# pcb1.net
KiCad netlist of a schematic drawn in EAGLE
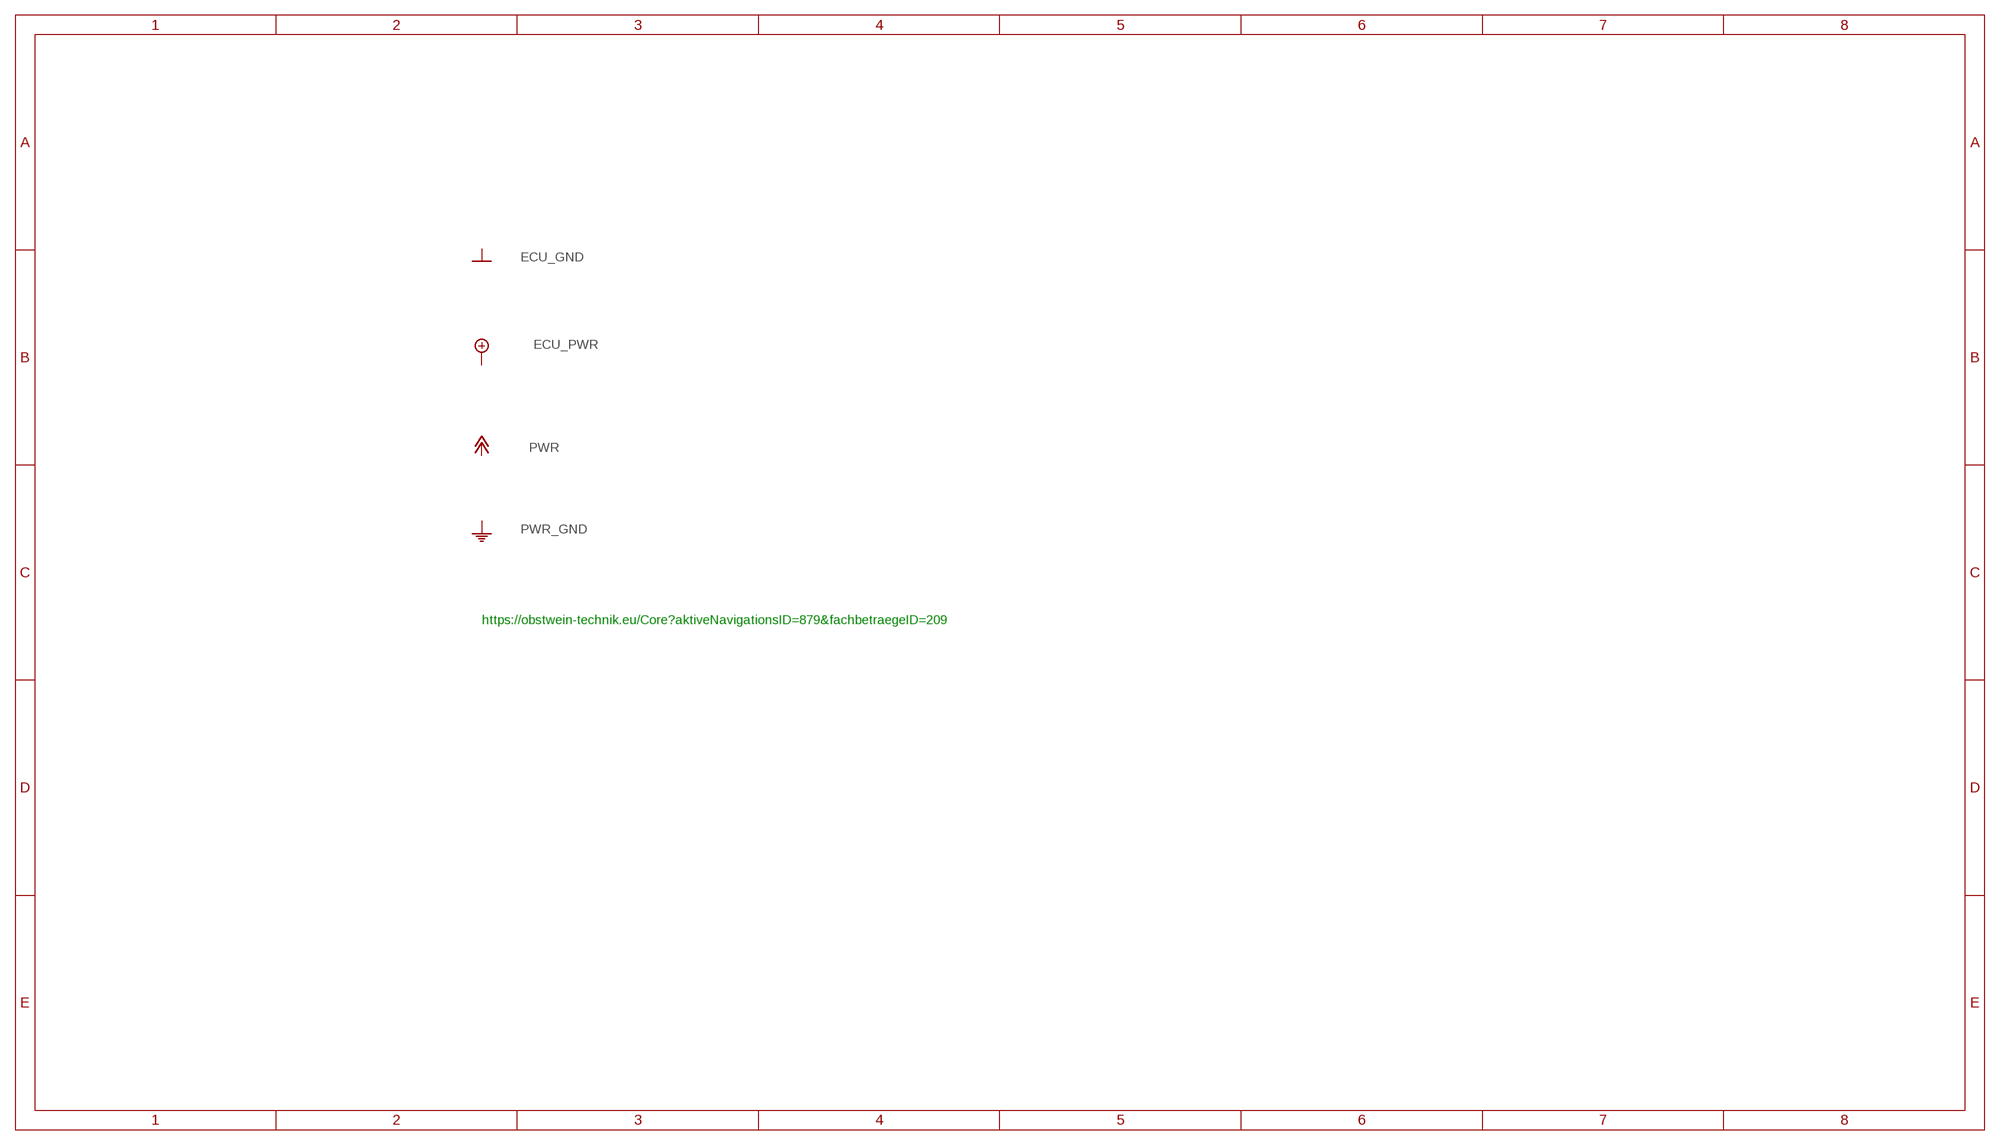
[diagram p0: schematic, sheet 1]
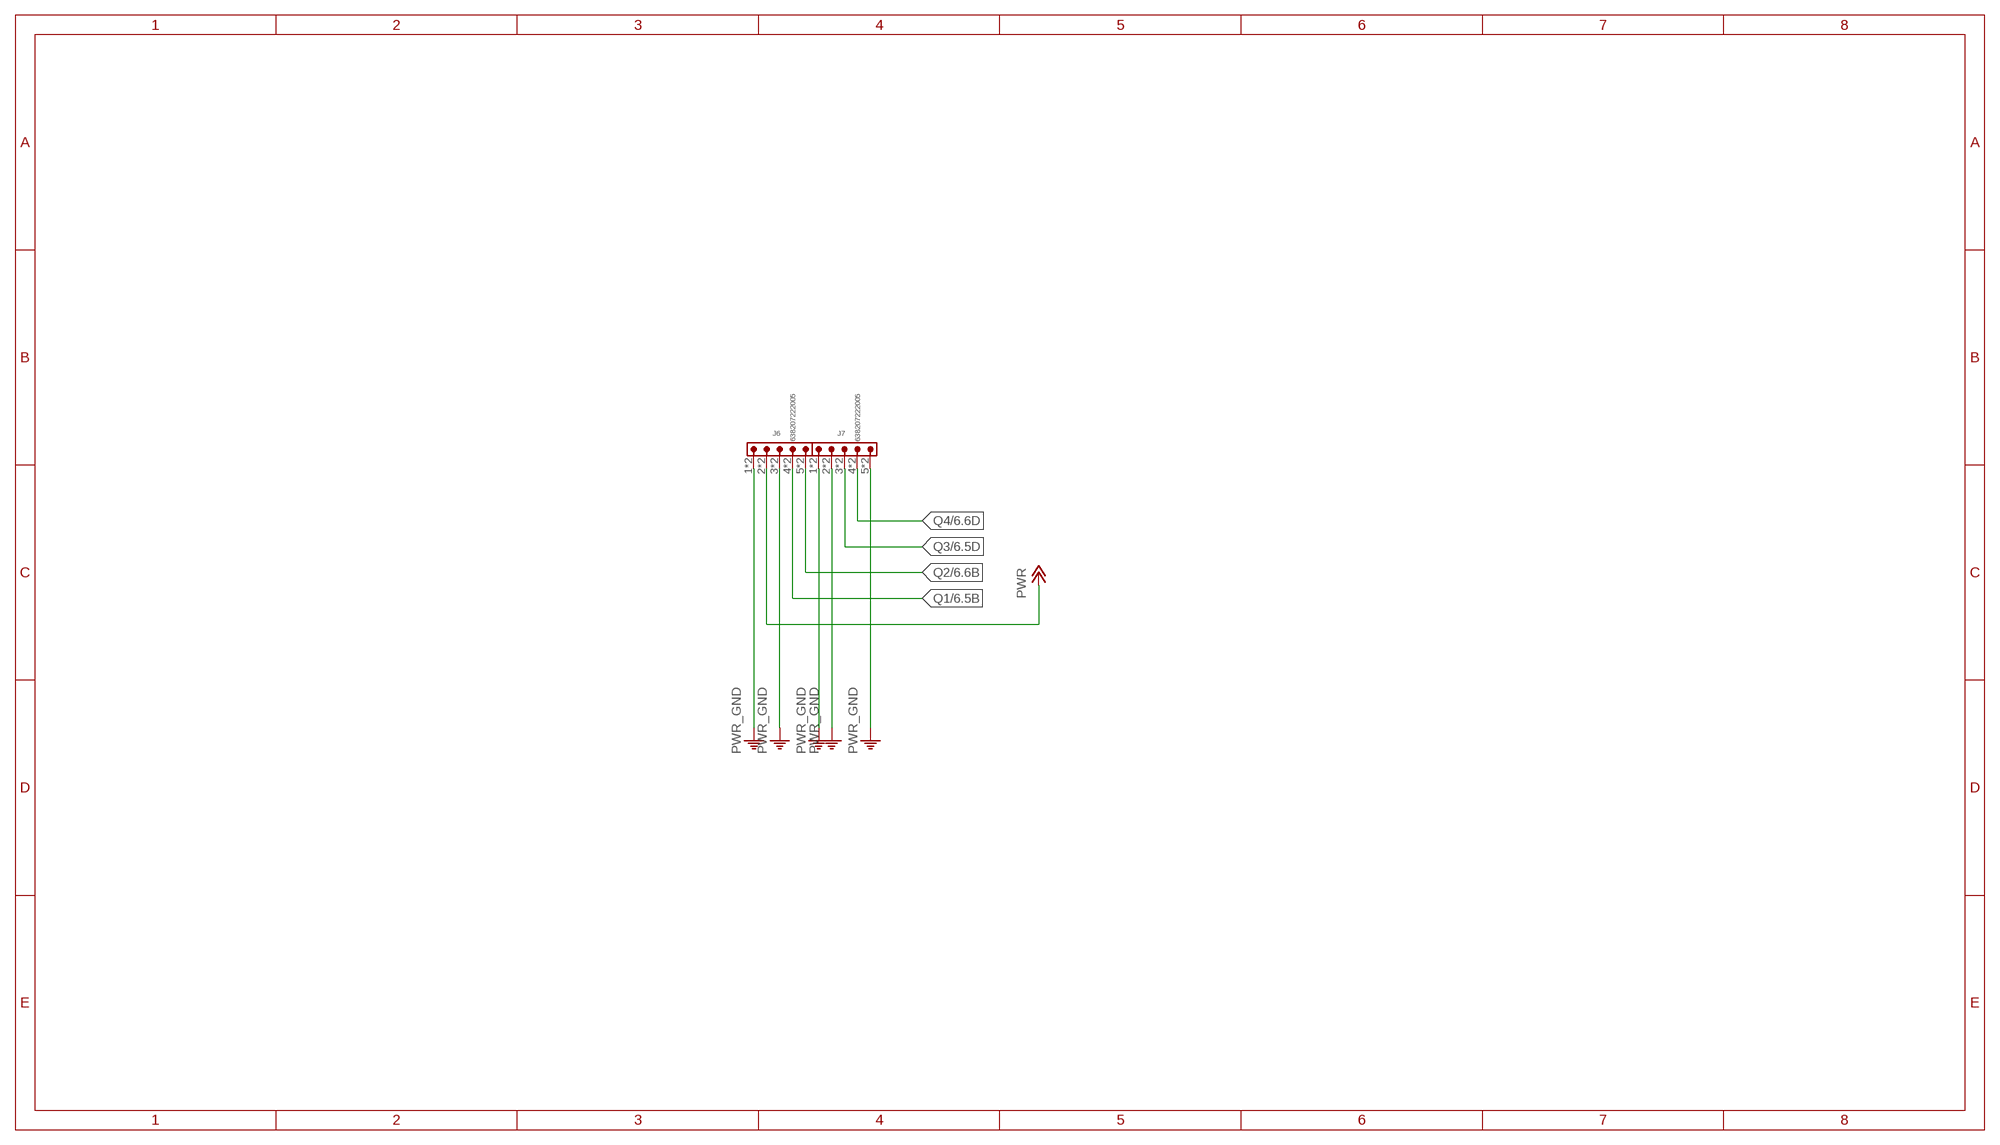
[diagram p1: schematic, sheet 2]
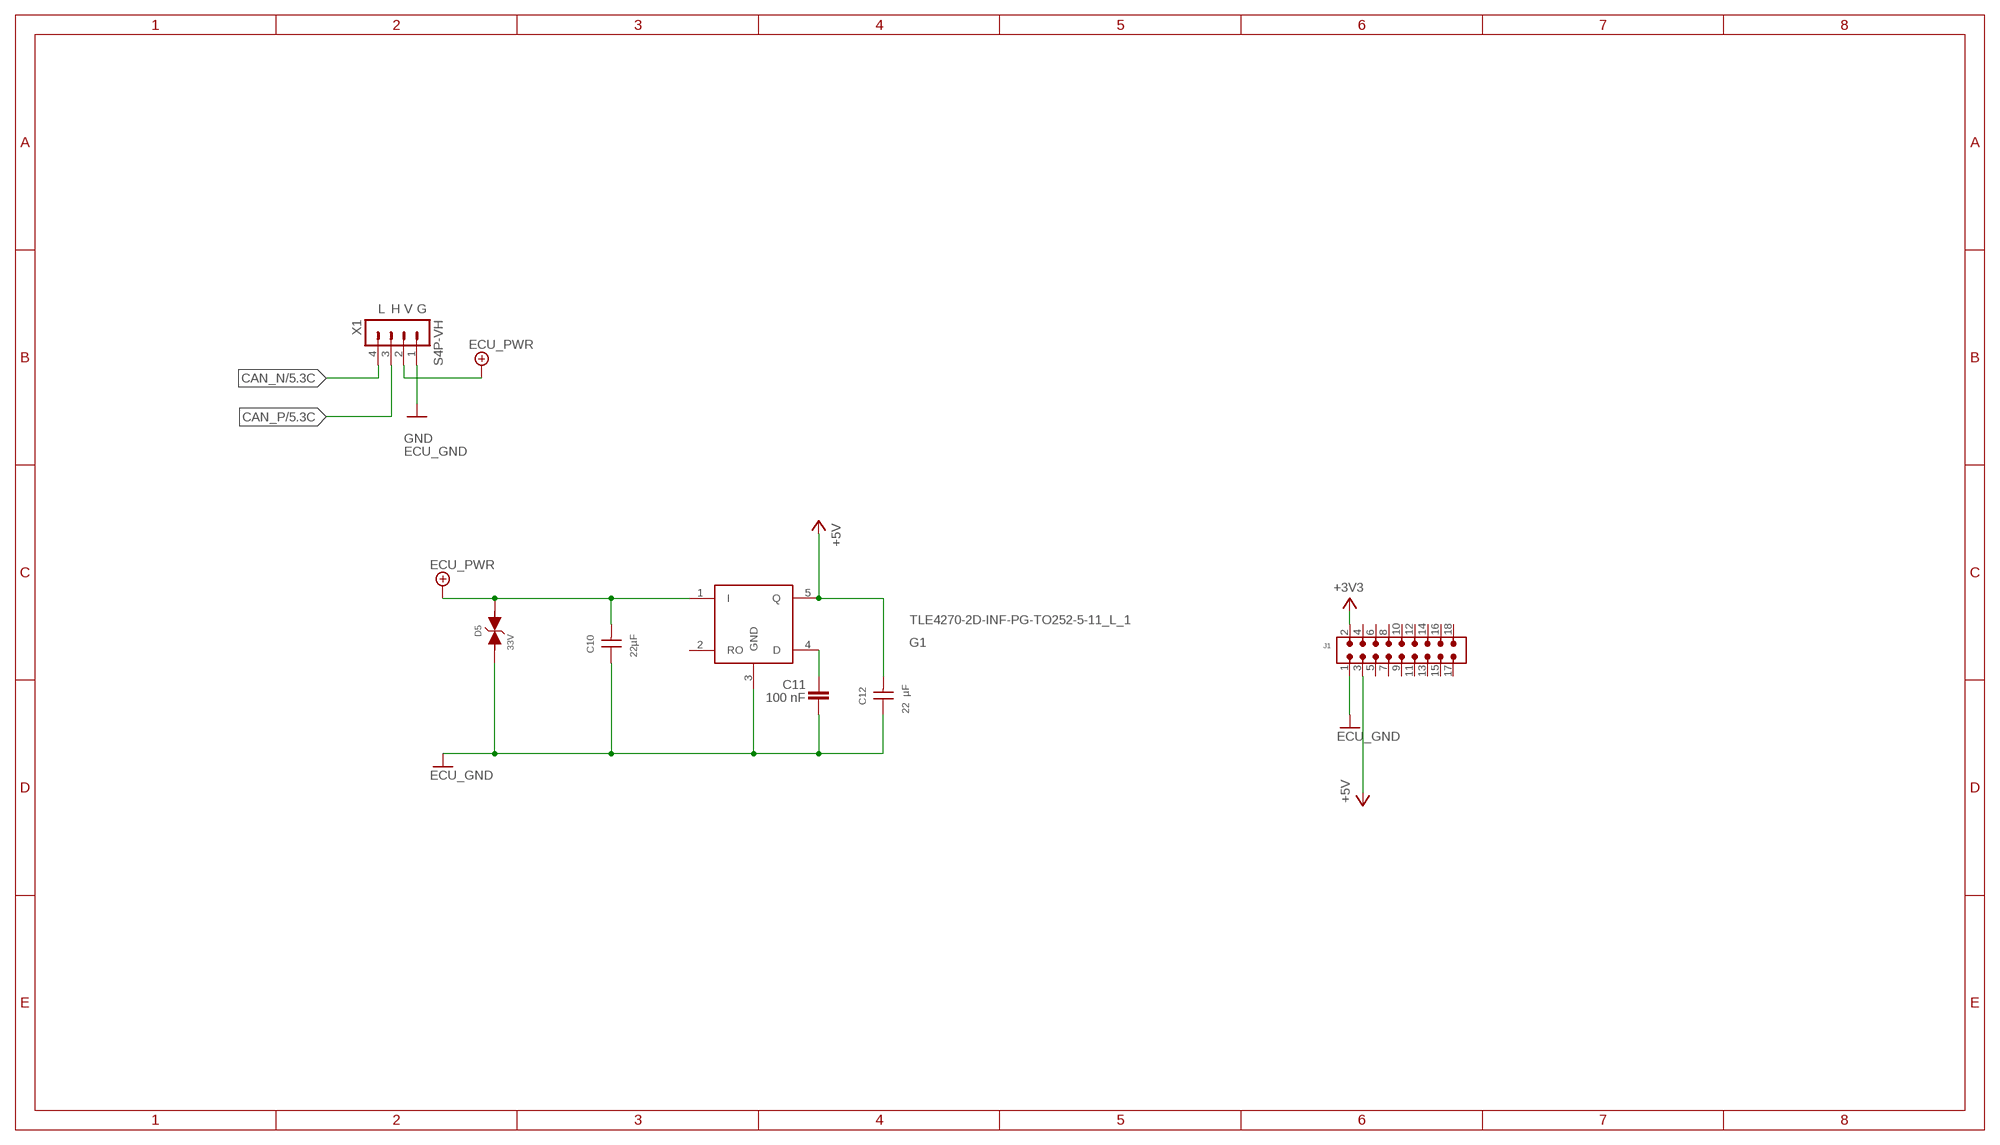
[diagram p2: schematic, sheet 3]
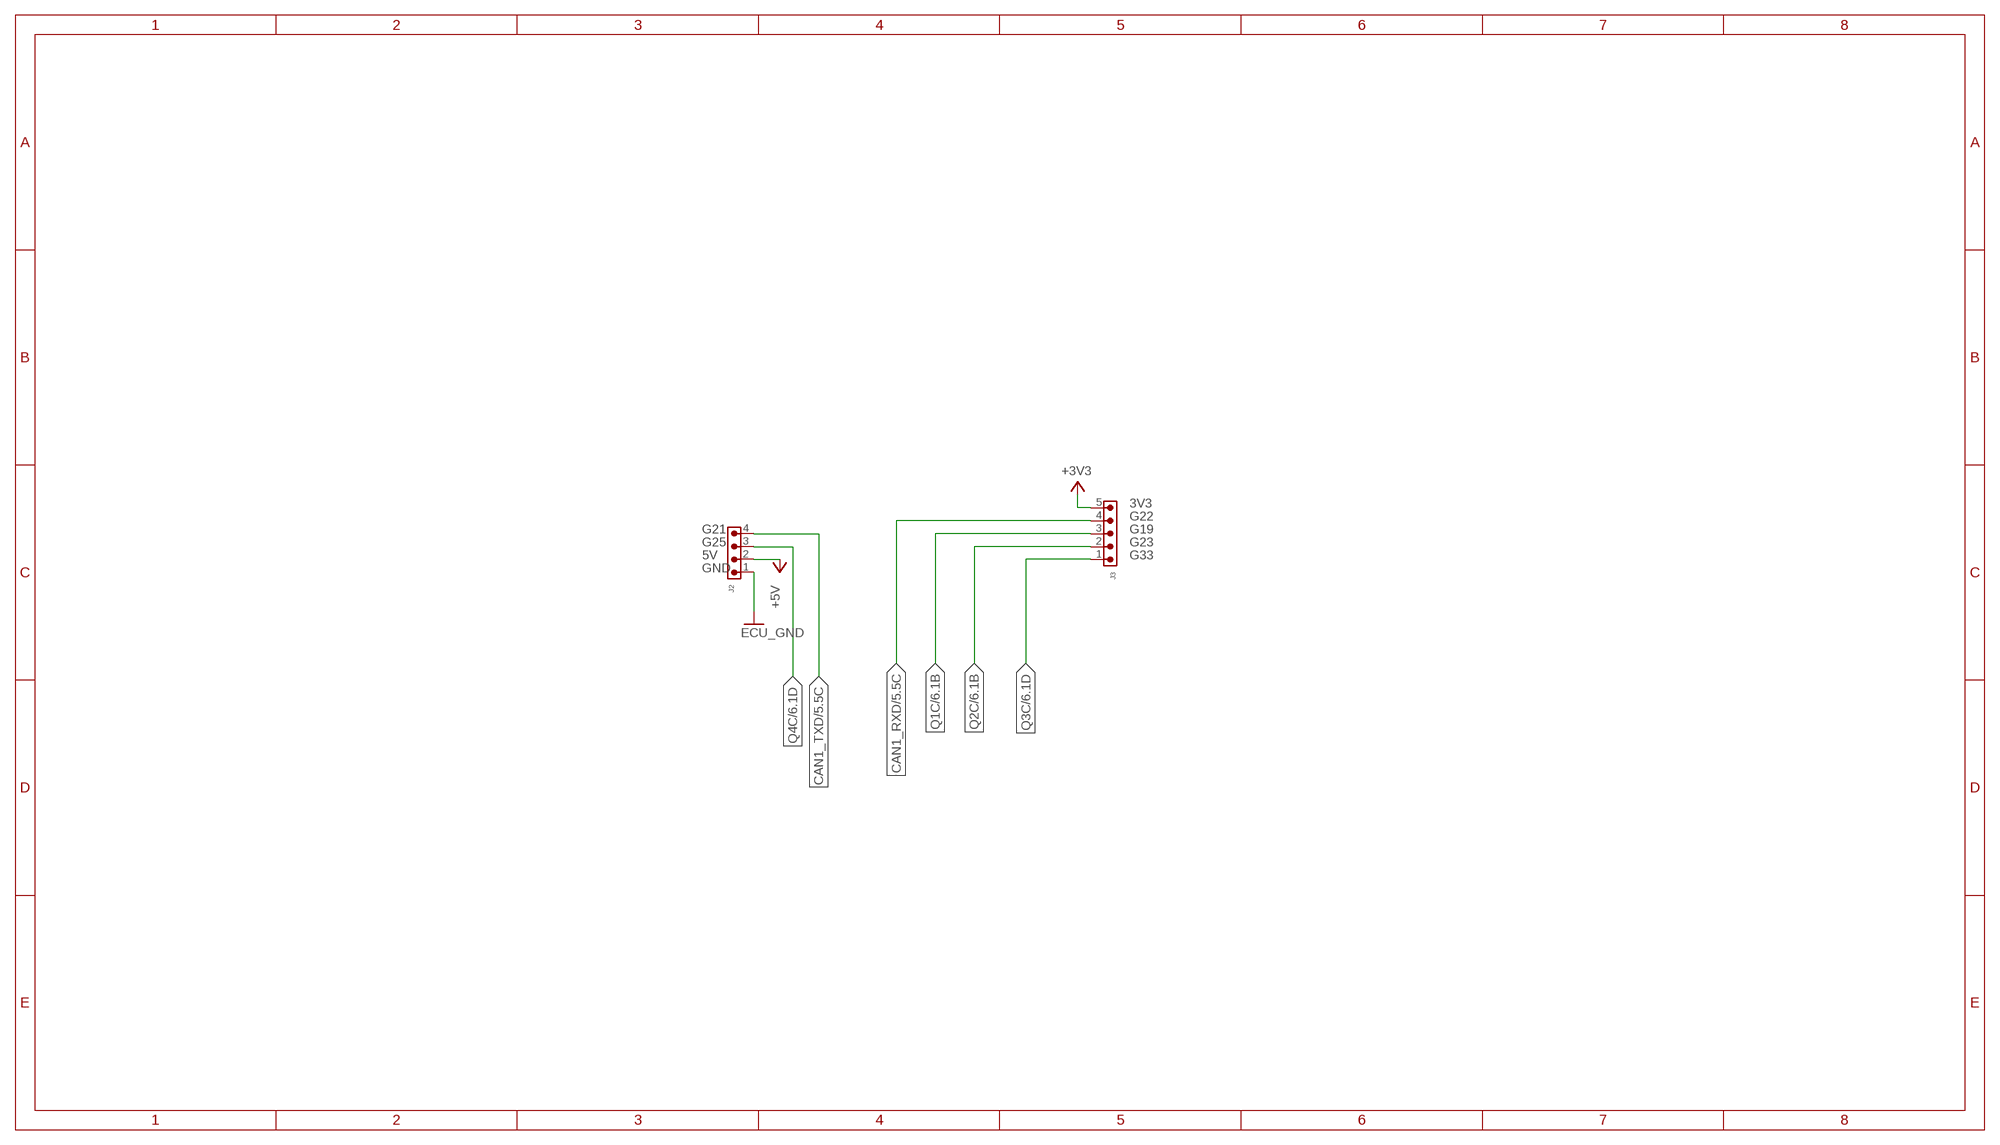
[diagram p3: schematic, sheet 4]
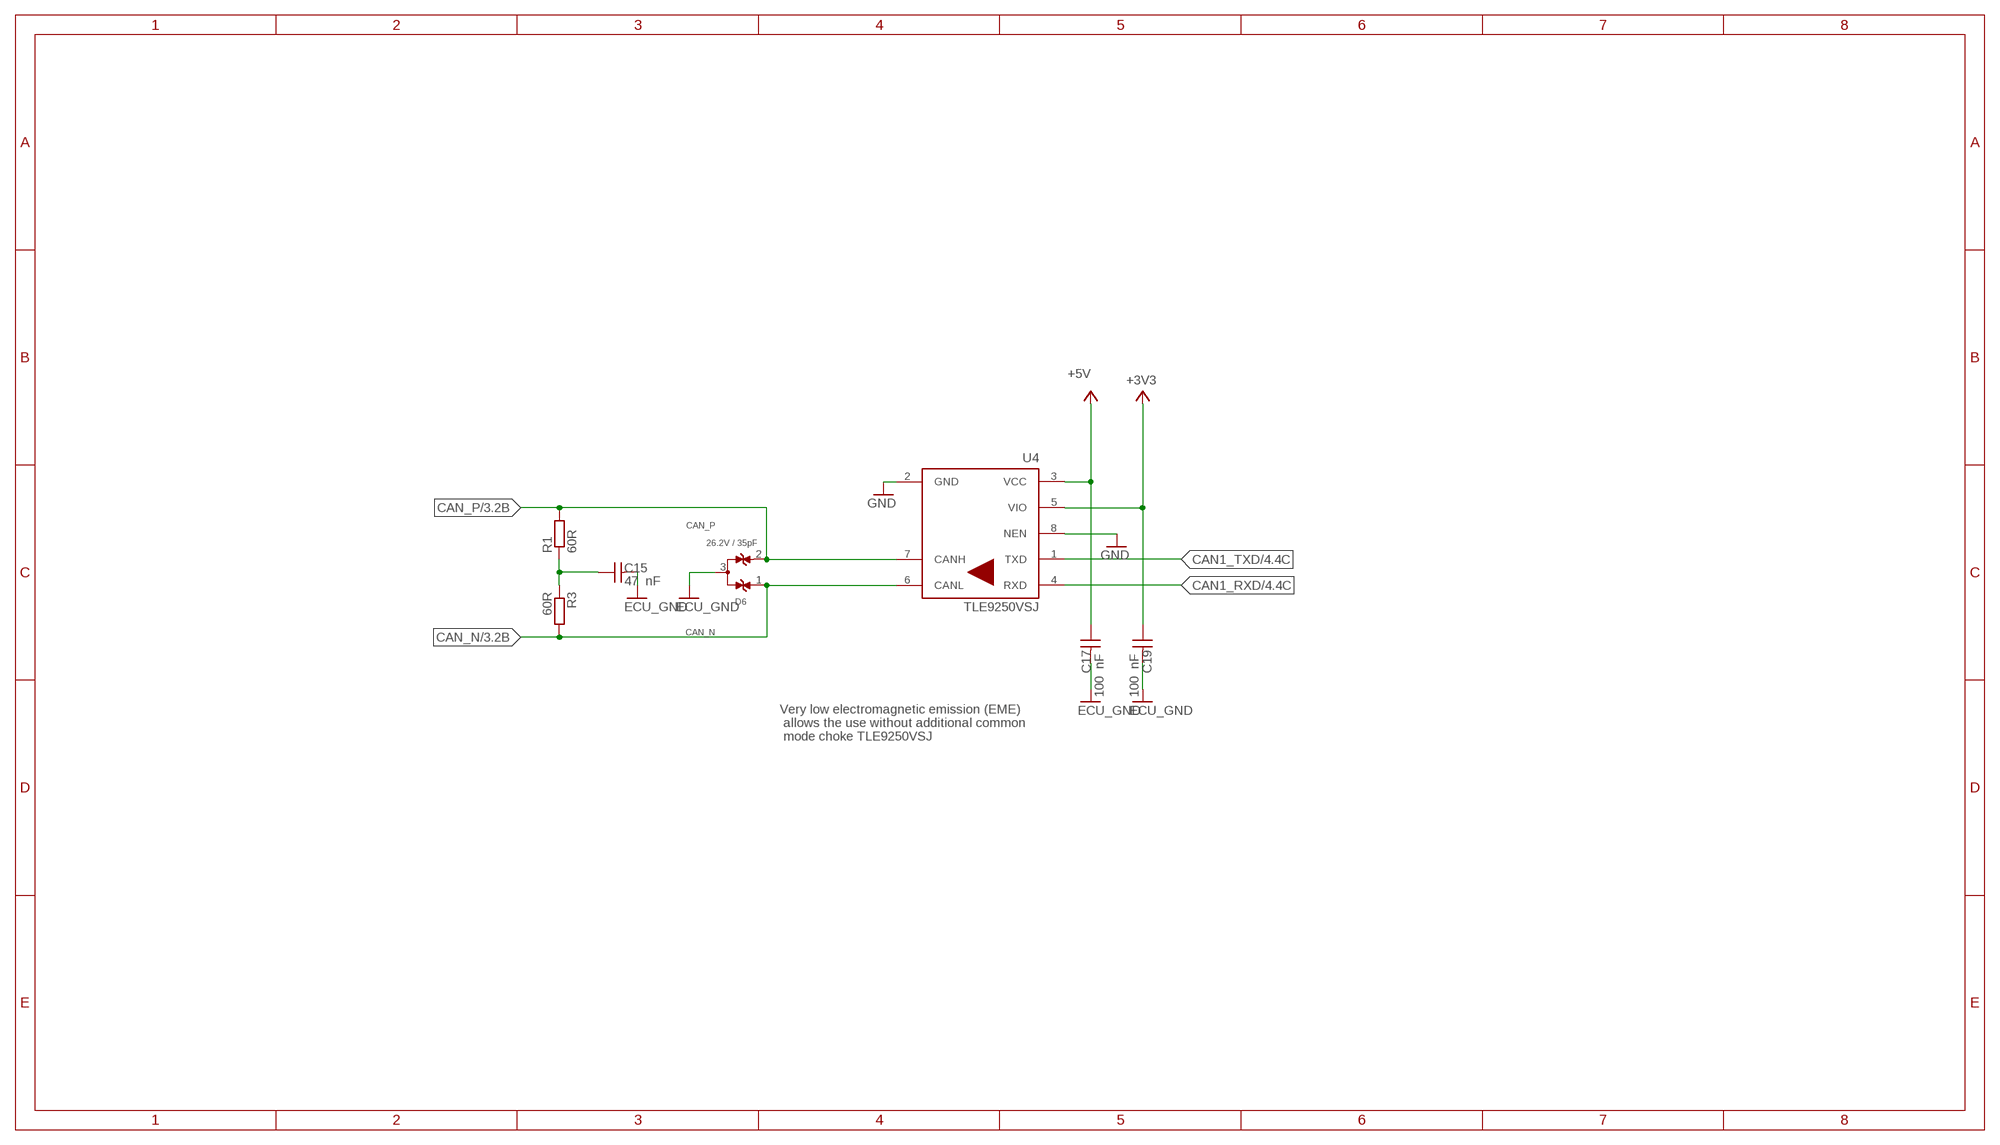
[diagram p4: schematic, sheet 5]
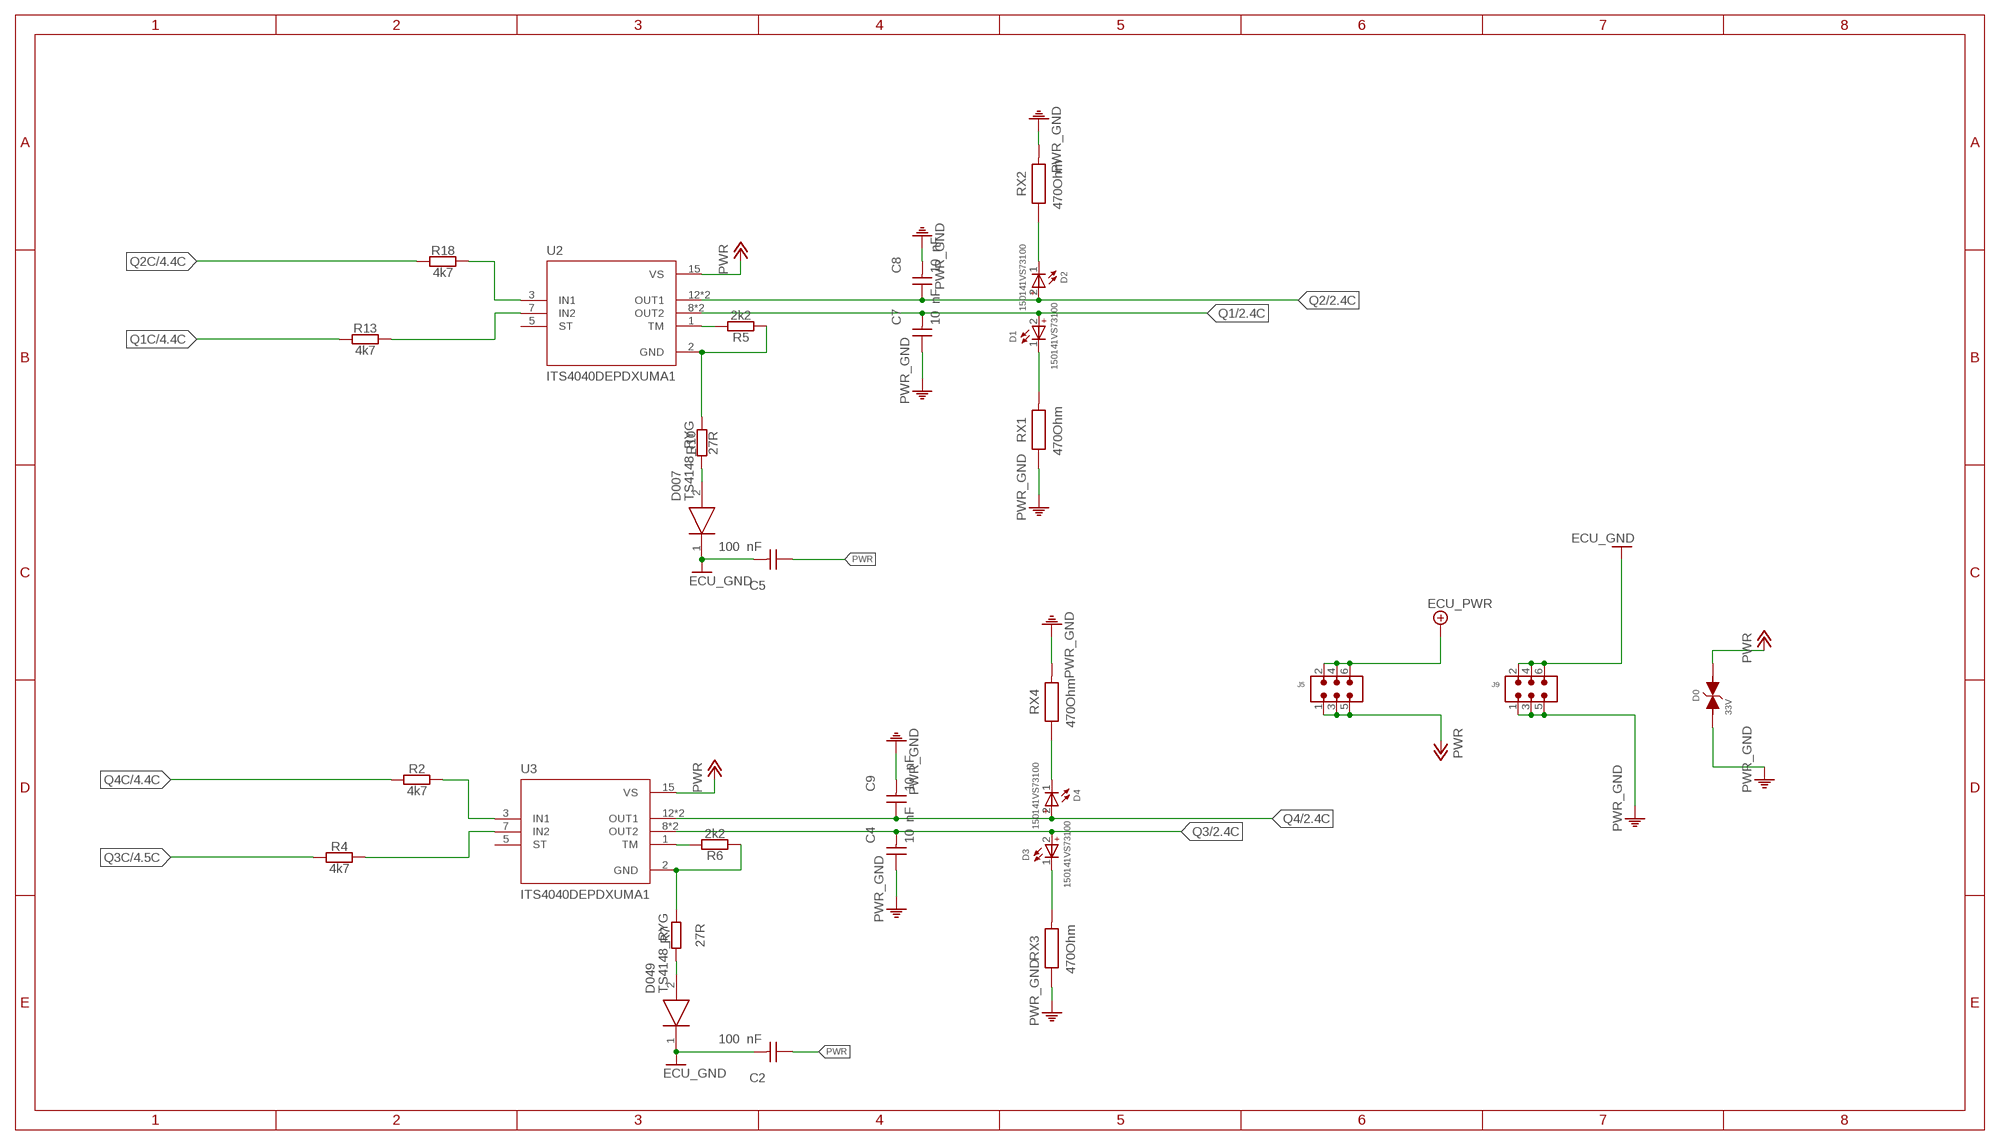
[diagram p5: schematic, sheet 6]

(export (version "E")
  (design (tool "Eeschema 10.0.6"))
  (components
    (comp (ref "C15")
      (value "47 nF")
      (footprint "eagle-import:WCAP-CSGP_0805_H0.8_R")
      (libsource (lib "eagle-import") (part "WCAP-CSGP_0805_H0.8_50V(DC)_R_885012207096"))
    )
    (comp (ref "C17")
      (value "100 nF")
      (footprint "eagle-import:WCAP-CSGP_0805_H0.8_R")
      (libsource (lib "eagle-import") (part "WCAP-CSGP_0805_H0.8_50V(DC)_R_885012207098"))
    )
    (comp (ref "C19")
      (value "100 nF")
      (footprint "eagle-import:WCAP-CSGP_0805_H0.8_R")
      (libsource (lib "eagle-import") (part "WCAP-CSGP_0805_H0.8_50V(DC)_R_885012207098"))
    )
    (comp (ref "D6")
      (value "26.2V / 35pF")
      (footprint "eagle-import:WE-TVS_SOT23-3L")
      (libsource (lib "eagle-import") (part "WE-TVS_SOT23-3L_824098024"))
    )
    (comp (ref "R1")
      (value "60R")
      (footprint "eagle-import:R0805")
      (libsource (lib "eagle-import") (part "R-EU_R0805"))
    )
    (comp (ref "R3")
      (value "60R")
      (footprint "eagle-import:R0805")
      (libsource (lib "eagle-import") (part "R-EU_R0805"))
    )
    (comp (ref "U4")
      (value "TLE9250VSJ")
      (footprint "eagle-import:SOIC127P602X173-8N-V")
      (libsource (lib "eagle-import") (part "TLE9250VSJ"))
    )
    (comp (ref "J2")
      (value "6130XX11121_61300411121")
      (footprint "eagle-import:61300411121")
      (libsource (lib "eagle-import") (part "6130XX11121_61300411121"))
    )
    (comp (ref "J3")
      (value "6130XX11121_61300511121")
      (footprint "eagle-import:61300511121")
      (libsource (lib "eagle-import") (part "6130XX11121_61300511121"))
    )
    (comp (ref "C10")
      (value "22µF")
      (footprint "eagle-import:WCAP-CSGP_1210_H2.5")
      (libsource (lib "eagle-import") (part "WCAP-CSGP_1210_H2.5_25V(DC)_885012109014"))
    )
    (comp (ref "C11")
      (value "100 nF")
      (footprint "eagle-import:WCAP-CSGP_0402")
      (libsource (lib "eagle-import") (part "WCAP-CSGP_0402_16V(DC)_885012205037"))
    )
    (comp (ref "C12")
      (value "22 µF")
      (footprint "eagle-import:WCAP-CSGP_0805_H1.25_R")
      (libsource (lib "eagle-import") (part "WCAP-CSGP_0805_H1.25_10V(DC)_885012107011"))
    )
    (comp (ref "D5")
      (value "33V")
      (footprint "eagle-import:WE-TVSP_DO-214AB_BIDIRECTIONAL")
      (libsource (lib "eagle-import") (part "WE-TVSP_DO-214AB_3000W_BI_824551331"))
    )
    (comp (ref "G1")
      (value "TLE4270-2D-INF-PG-TO252-5-11_L_1")
      (footprint "eagle-import:INF-PG-TO252-5-11_L_1PRIMARY")
      (libsource (lib "eagle-import") (part "TLE4270-2D-INF-PG-TO252-5-11_L_1"))
    )
    (comp (ref "J1")
      (value "6130XX21121_61301821121")
      (footprint "eagle-import:61301821121")
      (libsource (lib "eagle-import") (part "6130XX21121_61301821121"))
    )
    (comp (ref "X1")
      (value "S4P-VH")
      (footprint "eagle-import:S4P-VH")
      (libsource (lib "eagle-import") (part "S4P-VH"))
    )
    (comp (ref "J6")
      (value "638207222005")
      (footprint "eagle-import:638207222005")
      (libsource (lib "eagle-import") (part "638207222005"))
    )
    (comp (ref "J7")
      (value "638207222005")
      (footprint "eagle-import:638207222005")
      (libsource (lib "eagle-import") (part "638207222005"))
    )
    (comp (ref "C2")
      (value "100 nF")
      (footprint "eagle-import:WCAP-CSGP_0805_H0.8_R")
      (libsource (lib "eagle-import") (part "WCAP-CSGP_0805_H0.8_50V(DC)_R_885012207098"))
    )
    (comp (ref "C4")
      (value "10 nF")
      (footprint "eagle-import:WCAP-CSGP_0805_H0.8_R")
      (libsource (lib "eagle-import") (part "WCAP-CSGP_0805_H0.8_50V(DC)_R_885012207092"))
    )
    (comp (ref "C5")
      (value "100 nF")
      (footprint "eagle-import:WCAP-CSGP_0805_H0.8_R")
      (libsource (lib "eagle-import") (part "WCAP-CSGP_0805_H0.8_50V(DC)_R_885012207098"))
    )
    (comp (ref "C7")
      (value "10 nF")
      (footprint "eagle-import:WCAP-CSGP_0805_H0.8_R")
      (libsource (lib "eagle-import") (part "WCAP-CSGP_0805_H0.8_50V(DC)_R_885012207092"))
    )
    (comp (ref "C8")
      (value "10 nF")
      (footprint "eagle-import:WCAP-CSGP_0805_H0.8_R")
      (libsource (lib "eagle-import") (part "WCAP-CSGP_0805_H0.8_50V(DC)_R_885012207092"))
    )
    (comp (ref "C9")
      (value "10 nF")
      (footprint "eagle-import:WCAP-CSGP_0805_H0.8_R")
      (libsource (lib "eagle-import") (part "WCAP-CSGP_0805_H0.8_50V(DC)_R_885012207092"))
    )
    (comp (ref "D0")
      (value "33V")
      (footprint "eagle-import:WE-TVSP_DO-214AB_BIDIRECTIONAL")
      (libsource (lib "eagle-import") (part "WE-TVSP_DO-214AB_3000W_BI_824551331"))
    )
    (comp (ref "D1")
      (value "150141VS73100")
      (footprint "eagle-import:WL-SMTW_3528")
      (libsource (lib "eagle-import") (part "WL-SMTW_3528_150141VS73100"))
    )
    (comp (ref "D2")
      (value "150141VS73100")
      (footprint "eagle-import:WL-SMTW_3528")
      (libsource (lib "eagle-import") (part "WL-SMTW_3528_150141VS73100"))
    )
    (comp (ref "D3")
      (value "150141VS73100")
      (footprint "eagle-import:WL-SMTW_3528")
      (libsource (lib "eagle-import") (part "WL-SMTW_3528_150141VS73100"))
    )
    (comp (ref "D4")
      (value "150141VS73100")
      (footprint "eagle-import:WL-SMTW_3528")
      (libsource (lib "eagle-import") (part "WL-SMTW_3528_150141VS73100"))
    )
    (comp (ref "D007")
      (value "TS4148_RYG")
      (footprint "eagle-import:DIOC2012X95N")
      (fields
        (field (name "MANUFACTURER_PART_NUMBER") "TS4148 RYG")
        (field (name "MOUSER_PART_NUMBER") "821-TS4148RYG")
      )
      (libsource (lib "eagle-import") (part "TS4148_RYG"))
    )
    (comp (ref "D049")
      (value "TS4148_RYG")
      (footprint "eagle-import:DIOC2012X95N")
      (fields
        (field (name "MANUFACTURER_PART_NUMBER") "TS4148 RYG")
        (field (name "MOUSER_PART_NUMBER") "821-TS4148RYG")
      )
      (libsource (lib "eagle-import") (part "TS4148_RYG"))
    )
    (comp (ref "J5")
      (value "6130XX21121_61300621121")
      (footprint "eagle-import:61300621121")
      (libsource (lib "eagle-import") (part "6130XX21121_61300621121"))
    )
    (comp (ref "J9")
      (value "6130XX21121_61300621121")
      (footprint "eagle-import:61300621121")
      (libsource (lib "eagle-import") (part "6130XX21121_61300621121"))
    )
    (comp (ref "R2")
      (value "4k7")
      (footprint "eagle-import:R0805")
      (libsource (lib "eagle-import") (part "R-EU_R0805"))
    )
    (comp (ref "R4")
      (value "4k7")
      (footprint "eagle-import:R0805")
      (libsource (lib "eagle-import") (part "R-EU_R0805"))
    )
    (comp (ref "R5")
      (value "2k2")
      (footprint "eagle-import:R0805")
      (libsource (lib "eagle-import") (part "R-EU_R0805"))
    )
    (comp (ref "R6")
      (value "2k2")
      (footprint "eagle-import:R0805")
      (libsource (lib "eagle-import") (part "R-EU_R0805"))
    )
    (comp (ref "R7")
      (value "27R")
      (footprint "eagle-import:R0805")
      (libsource (lib "eagle-import") (part "R-EU_R0805"))
    )
    (comp (ref "R10")
      (value "27R")
      (footprint "eagle-import:R0805")
      (libsource (lib "eagle-import") (part "R-EU_R0805"))
    )
    (comp (ref "R13")
      (value "4k7")
      (footprint "eagle-import:R0805")
      (libsource (lib "eagle-import") (part "R-EU_R0805"))
    )
    (comp (ref "R18")
      (value "4k7")
      (footprint "eagle-import:R0805")
      (libsource (lib "eagle-import") (part "R-EU_R0805"))
    )
    (comp (ref "RX1")
      (value "470Ohm")
      (footprint "eagle-import:WRIS-KWKB_0612")
      (libsource (lib "eagle-import") (part "WRIS-KWKB_0612_561020132023"))
    )
    (comp (ref "RX2")
      (value "470Ohm")
      (footprint "eagle-import:WRIS-KWKB_0612")
      (libsource (lib "eagle-import") (part "WRIS-KWKB_0612_561020132023"))
    )
    (comp (ref "RX3")
      (value "470Ohm")
      (footprint "eagle-import:WRIS-KWKB_0612")
      (libsource (lib "eagle-import") (part "WRIS-KWKB_0612_561020132023"))
    )
    (comp (ref "RX4")
      (value "470Ohm")
      (footprint "eagle-import:WRIS-KWKB_0612")
      (libsource (lib "eagle-import") (part "WRIS-KWKB_0612_561020132023"))
    )
    (comp (ref "U2")
      (value "ITS4040DEPDXUMA1")
      (footprint "eagle-import:SOP65P600X115-15N")
      (fields
        (field (name "DIGI-KEY_PART_NUMBER") "ITS4040DEPDXUMA1TR-ND")
        (field (name "MF") "Infineon Technologies")
      )
      (libsource (lib "eagle-import") (part "ITS4040DEPDXUMA1"))
    )
    (comp (ref "U3")
      (value "ITS4040DEPDXUMA1")
      (footprint "eagle-import:SOP65P600X115-15N")
      (fields
        (field (name "DIGI-KEY_PART_NUMBER") "ITS4040DEPDXUMA1TR-ND")
        (field (name "MF") "Infineon Technologies")
      )
      (libsource (lib "eagle-import") (part "ITS4040DEPDXUMA1"))
    )
  )
  (nets
    (net (code "1") (name "+3V3") (class "Default")
      (node (ref "C19") (pin "1") (pinfunction "1_1") (pintype "passive"))
      (node (ref "J1") (pin "2") (pinfunction "2_2") (pintype "passive"))
      (node (ref "J3") (pin "5") (pinfunction "5_5") (pintype "passive"))
      (node (ref "U4") (pin "5") (pinfunction "VIO_5") (pintype "input"))
    )
    (net (code "2") (name "+5V") (class "Default")
      (node (ref "C12") (pin "2") (pinfunction "2_2") (pintype "passive"))
      (node (ref "C17") (pin "1") (pinfunction "1_1") (pintype "passive"))
      (node (ref "G1") (pin "5") (pinfunction "Q_5") (pintype "power_in"))
      (node (ref "J1") (pin "3") (pinfunction "3_3") (pintype "passive"))
      (node (ref "J2") (pin "2") (pinfunction "2_2") (pintype "passive"))
      (node (ref "U4") (pin "3") (pinfunction "VCC_3") (pintype "input"))
    )
    (net (code "3") (name "CAN1_RXD") (class "Default")
      (node (ref "J3") (pin "4") (pinfunction "4_4") (pintype "passive"))
      (node (ref "U4") (pin "4") (pinfunction "RXD_4") (pintype "output"))
    )
    (net (code "4") (name "CAN1_TXD") (class "Default")
      (node (ref "J2") (pin "4") (pinfunction "4_4") (pintype "passive"))
      (node (ref "U4") (pin "1") (pinfunction "TXD_1") (pintype "input"))
    )
    (net (code "5") (name "CAN_N") (class "Default")
      (node (ref "D6") (pin "1") (pinfunction "1_1") (pintype "passive"))
      (node (ref "R3") (pin "2") (pinfunction "2_2") (pintype "passive"))
      (node (ref "U4") (pin "6") (pinfunction "CANL_6") (pintype "bidirectional"))
      (node (ref "X1") (pin "4") (pinfunction "4_4") (pintype "passive"))
    )
    (net (code "6") (name "CAN_P") (class "Default")
      (node (ref "D6") (pin "2") (pinfunction "2_2") (pintype "passive"))
      (node (ref "R1") (pin "2") (pinfunction "2_2") (pintype "passive"))
      (node (ref "U4") (pin "7") (pinfunction "CANH_7") (pintype "bidirectional"))
      (node (ref "X1") (pin "3") (pinfunction "3_3") (pintype "passive"))
    )
    (net (code "7") (name "ECU_GND") (class "Default")
      (node (ref "C10") (pin "1") (pinfunction "1_1") (pintype "passive"))
      (node (ref "C11") (pin "2") (pinfunction "2_2") (pintype "passive"))
      (node (ref "C12") (pin "1") (pinfunction "1_1") (pintype "passive"))
      (node (ref "C15") (pin "2") (pinfunction "2_2") (pintype "passive"))
      (node (ref "C17") (pin "2") (pinfunction "2_2") (pintype "passive"))
      (node (ref "C19") (pin "2") (pinfunction "2_2") (pintype "passive"))
      (node (ref "C2") (pin "2") (pinfunction "2_2") (pintype "passive"))
      (node (ref "C5") (pin "2") (pinfunction "2_2") (pintype "passive"))
      (node (ref "D007") (pin "1") (pinfunction "K_1") (pintype "bidirectional"))
      (node (ref "D049") (pin "1") (pinfunction "K_1") (pintype "bidirectional"))
      (node (ref "D5") (pin "1") (pinfunction "1_1") (pintype "passive"))
      (node (ref "D6") (pin "3") (pinfunction "3_3") (pintype "passive"))
      (node (ref "G1") (pin "3") (pinfunction "GND_3") (pintype "power_in"))
      (node (ref "J1") (pin "1") (pinfunction "1_1") (pintype "passive"))
      (node (ref "J2") (pin "1") (pinfunction "1_1") (pintype "passive"))
      (node (ref "J9") (pin "2") (pinfunction "2_2") (pintype "passive"))
      (node (ref "J9") (pin "4") (pinfunction "4_4") (pintype "passive"))
      (node (ref "J9") (pin "6") (pinfunction "6_6") (pintype "passive"))
      (node (ref "U4") (pin "2") (pinfunction "GND_2") (pintype "power_in"))
      (node (ref "U4") (pin "8") (pinfunction "NEN_8") (pintype "input"))
      (node (ref "X1") (pin "1") (pinfunction "1_1") (pintype "passive"))
    )
    (net (code "8") (name "ECU_PWR") (class "Default")
      (node (ref "C10") (pin "2") (pinfunction "2_2") (pintype "passive"))
      (node (ref "D5") (pin "2") (pinfunction "2_2") (pintype "passive"))
      (node (ref "G1") (pin "1") (pinfunction "I_1") (pintype "power_in"))
      (node (ref "J5") (pin "2") (pinfunction "2_2") (pintype "passive"))
      (node (ref "J5") (pin "4") (pinfunction "4_4") (pintype "passive"))
      (node (ref "J5") (pin "6") (pinfunction "6_6") (pintype "passive"))
      (node (ref "X1") (pin "2") (pinfunction "2_2") (pintype "passive"))
    )
    (net (code "9") (name "Net-(C15-Pad1)") (class "Default")
      (node (ref "C15") (pin "1") (pinfunction "1_1") (pintype "passive"))
      (node (ref "R1") (pin "1") (pinfunction "1_1") (pintype "passive"))
      (node (ref "R3") (pin "1") (pinfunction "1_1") (pintype "passive"))
    )
    (net (code "10") (name "Net-(D1--)") (class "Default")
      (node (ref "D1") (pin "1") (pinfunction "-_1") (pintype "passive"))
      (node (ref "RX1") (pin "2") (pinfunction "2_2") (pintype "passive"))
    )
    (net (code "11") (name "Net-(D2--)") (class "Default")
      (node (ref "D2") (pin "1") (pinfunction "-_1") (pintype "passive"))
      (node (ref "RX2") (pin "1") (pinfunction "1_1") (pintype "passive"))
    )
    (net (code "12") (name "Net-(D3--)") (class "Default")
      (node (ref "D3") (pin "1") (pinfunction "-_1") (pintype "passive"))
      (node (ref "RX3") (pin "2") (pinfunction "2_2") (pintype "passive"))
    )
    (net (code "13") (name "Net-(D4--)") (class "Default")
      (node (ref "D4") (pin "1") (pinfunction "-_1") (pintype "passive"))
      (node (ref "RX4") (pin "1") (pinfunction "1_1") (pintype "passive"))
    )
    (net (code "14") (name "Net-(D007-A)") (class "Default")
      (node (ref "D007") (pin "2") (pinfunction "A_2") (pintype "bidirectional"))
      (node (ref "R10") (pin "1") (pinfunction "1_1") (pintype "passive"))
    )
    (net (code "15") (name "Net-(D049-A)") (class "Default")
      (node (ref "D049") (pin "2") (pinfunction "A_2") (pintype "bidirectional"))
      (node (ref "R7") (pin "1") (pinfunction "1_1") (pintype "passive"))
    )
    (net (code "16") (name "Net-(G1-D)") (class "Default")
      (node (ref "C11") (pin "1") (pinfunction "1_1") (pintype "passive"))
      (node (ref "G1") (pin "4") (pinfunction "D_4") (pintype "bidirectional"))
    )
    (net (code "17") (name "Net-(U2-GND)") (class "Default")
      (node (ref "R10") (pin "2") (pinfunction "2_2") (pintype "passive"))
      (node (ref "R5") (pin "1") (pinfunction "1_1") (pintype "passive"))
      (node (ref "U2") (pin "2") (pinfunction "GND_2") (pintype "power_in"))
    )
    (net (code "18") (name "Net-(U2-IN1)") (class "Default")
      (node (ref "R18") (pin "2") (pinfunction "2_2") (pintype "passive"))
      (node (ref "U2") (pin "3") (pinfunction "IN1_3") (pintype "input"))
    )
    (net (code "19") (name "Net-(U2-IN2)") (class "Default")
      (node (ref "R13") (pin "2") (pinfunction "2_2") (pintype "passive"))
      (node (ref "U2") (pin "7") (pinfunction "IN2_7") (pintype "input"))
    )
    (net (code "20") (name "Net-(U2-TM)") (class "Default")
      (node (ref "R5") (pin "2") (pinfunction "2_2") (pintype "passive"))
      (node (ref "U2") (pin "1") (pinfunction "TM_1") (pintype "passive"))
    )
    (net (code "21") (name "Net-(U3-GND)") (class "Default")
      (node (ref "R6") (pin "1") (pinfunction "1_1") (pintype "passive"))
      (node (ref "R7") (pin "2") (pinfunction "2_2") (pintype "passive"))
      (node (ref "U3") (pin "2") (pinfunction "GND_2") (pintype "power_in"))
    )
    (net (code "22") (name "Net-(U3-IN1)") (class "Default")
      (node (ref "R2") (pin "2") (pinfunction "2_2") (pintype "passive"))
      (node (ref "U3") (pin "3") (pinfunction "IN1_3") (pintype "input"))
    )
    (net (code "23") (name "Net-(U3-IN2)") (class "Default")
      (node (ref "R4") (pin "2") (pinfunction "2_2") (pintype "passive"))
      (node (ref "U3") (pin "7") (pinfunction "IN2_7") (pintype "input"))
    )
    (net (code "24") (name "Net-(U3-TM)") (class "Default")
      (node (ref "R6") (pin "2") (pinfunction "2_2") (pintype "passive"))
      (node (ref "U3") (pin "1") (pinfunction "TM_1") (pintype "passive"))
    )
    (net (code "25") (name "PWR") (class "Default")
      (node (ref "C2") (pin "1") (pinfunction "1_1") (pintype "passive"))
      (node (ref "C5") (pin "1") (pinfunction "1_1") (pintype "passive"))
      (node (ref "D0") (pin "2") (pinfunction "2_2") (pintype "passive"))
      (node (ref "J5") (pin "1") (pinfunction "1_1") (pintype "passive"))
      (node (ref "J5") (pin "3") (pinfunction "3_3") (pintype "passive"))
      (node (ref "J5") (pin "5") (pinfunction "5_5") (pintype "passive"))
      (node (ref "J6") (pin "2") (pinfunction "2_2") (pintype "passive"))
      (node (ref "J6") (pin "A2") (pinfunction "2_A2") (pintype "passive"))
      (node (ref "U2") (pin "15") (pinfunction "VS_15") (pintype "power_in"))
      (node (ref "U3") (pin "15") (pinfunction "VS_15") (pintype "power_in"))
    )
    (net (code "26") (name "PWR_GND") (class "Default")
      (node (ref "C4") (pin "1") (pinfunction "1_1") (pintype "passive"))
      (node (ref "C7") (pin "1") (pinfunction "1_1") (pintype "passive"))
      (node (ref "C8") (pin "2") (pinfunction "2_2") (pintype "passive"))
      (node (ref "C9") (pin "2") (pinfunction "2_2") (pintype "passive"))
      (node (ref "D0") (pin "1") (pinfunction "1_1") (pintype "passive"))
      (node (ref "J6") (pin "1") (pinfunction "1_1") (pintype "passive"))
      (node (ref "J6") (pin "3") (pinfunction "3_3") (pintype "passive"))
      (node (ref "J6") (pin "A1") (pinfunction "1_A1") (pintype "passive"))
      (node (ref "J6") (pin "A3") (pinfunction "3_A3") (pintype "passive"))
      (node (ref "J7") (pin "1") (pinfunction "1_1") (pintype "passive"))
      (node (ref "J7") (pin "2") (pinfunction "2_2") (pintype "passive"))
      (node (ref "J7") (pin "5") (pinfunction "5_5") (pintype "passive"))
      (node (ref "J7") (pin "A1") (pinfunction "1_A1") (pintype "passive"))
      (node (ref "J7") (pin "A2") (pinfunction "2_A2") (pintype "passive"))
      (node (ref "J7") (pin "A5") (pinfunction "5_A5") (pintype "passive"))
      (node (ref "J9") (pin "1") (pinfunction "1_1") (pintype "passive"))
      (node (ref "J9") (pin "3") (pinfunction "3_3") (pintype "passive"))
      (node (ref "J9") (pin "5") (pinfunction "5_5") (pintype "passive"))
      (node (ref "RX1") (pin "1") (pinfunction "1_1") (pintype "passive"))
      (node (ref "RX2") (pin "2") (pinfunction "2_2") (pintype "passive"))
      (node (ref "RX3") (pin "1") (pinfunction "1_1") (pintype "passive"))
      (node (ref "RX4") (pin "2") (pinfunction "2_2") (pintype "passive"))
    )
    (net (code "27") (name "Q1") (class "Default")
      (node (ref "C7") (pin "2") (pinfunction "2_2") (pintype "passive"))
      (node (ref "D1") (pin "2") (pinfunction "+_2") (pintype "passive"))
      (node (ref "J6") (pin "4") (pinfunction "4_4") (pintype "passive"))
      (node (ref "J6") (pin "A4") (pinfunction "4_A4") (pintype "passive"))
      (node (ref "U2") (pin "10") (pinfunction "OUT2_10") (pintype "output"))
      (node (ref "U2") (pin "8") (pinfunction "OUT2_8") (pintype "output"))
    )
    (net (code "28") (name "Q1C") (class "Default")
      (node (ref "J3") (pin "3") (pinfunction "3_3") (pintype "passive"))
      (node (ref "R13") (pin "1") (pinfunction "1_1") (pintype "passive"))
    )
    (net (code "29") (name "Q2") (class "Default")
      (node (ref "C8") (pin "1") (pinfunction "1_1") (pintype "passive"))
      (node (ref "D2") (pin "2") (pinfunction "+_2") (pintype "passive"))
      (node (ref "J6") (pin "5") (pinfunction "5_5") (pintype "passive"))
      (node (ref "J6") (pin "A5") (pinfunction "5_A5") (pintype "passive"))
      (node (ref "U2") (pin "12") (pinfunction "OUT1_12") (pintype "output"))
      (node (ref "U2") (pin "14") (pinfunction "OUT1_14") (pintype "output"))
    )
    (net (code "30") (name "Q2C") (class "Default")
      (node (ref "J3") (pin "2") (pinfunction "2_2") (pintype "passive"))
      (node (ref "R18") (pin "1") (pinfunction "1_1") (pintype "passive"))
    )
    (net (code "31") (name "Q3") (class "Default")
      (node (ref "C4") (pin "2") (pinfunction "2_2") (pintype "passive"))
      (node (ref "D3") (pin "2") (pinfunction "+_2") (pintype "passive"))
      (node (ref "J7") (pin "3") (pinfunction "3_3") (pintype "passive"))
      (node (ref "J7") (pin "A3") (pinfunction "3_A3") (pintype "passive"))
      (node (ref "U3") (pin "10") (pinfunction "OUT2_10") (pintype "output"))
      (node (ref "U3") (pin "8") (pinfunction "OUT2_8") (pintype "output"))
    )
    (net (code "32") (name "Q3C") (class "Default")
      (node (ref "J3") (pin "1") (pinfunction "1_1") (pintype "passive"))
      (node (ref "R4") (pin "1") (pinfunction "1_1") (pintype "passive"))
    )
    (net (code "33") (name "Q4") (class "Default")
      (node (ref "C9") (pin "1") (pinfunction "1_1") (pintype "passive"))
      (node (ref "D4") (pin "2") (pinfunction "+_2") (pintype "passive"))
      (node (ref "J7") (pin "4") (pinfunction "4_4") (pintype "passive"))
      (node (ref "J7") (pin "A4") (pinfunction "4_A4") (pintype "passive"))
      (node (ref "U3") (pin "12") (pinfunction "OUT1_12") (pintype "output"))
      (node (ref "U3") (pin "14") (pinfunction "OUT1_14") (pintype "output"))
    )
    (net (code "34") (name "Q4C") (class "Default")
      (node (ref "J2") (pin "3") (pinfunction "3_3") (pintype "passive"))
      (node (ref "R2") (pin "1") (pinfunction "1_1") (pintype "passive"))
    )
    (net (code "35") (name "unconnected-(G1-RO-Pad2)") (class "Default")
      (node (ref "G1") (pin "2") (pinfunction "RO_2") (pintype "output"))
    )
    (net (code "36") (name "unconnected-(J1-Pad4)") (class "Default")
      (node (ref "J1") (pin "4") (pinfunction "4_4") (pintype "passive"))
    )
    (net (code "37") (name "unconnected-(J1-Pad5)") (class "Default")
      (node (ref "J1") (pin "5") (pinfunction "5_5") (pintype "passive"))
    )
    (net (code "38") (name "unconnected-(J1-Pad6)") (class "Default")
      (node (ref "J1") (pin "6") (pinfunction "6_6") (pintype "passive"))
    )
    (net (code "39") (name "unconnected-(J1-Pad7)") (class "Default")
      (node (ref "J1") (pin "7") (pinfunction "7_7") (pintype "passive"))
    )
    (net (code "40") (name "unconnected-(J1-Pad8)") (class "Default")
      (node (ref "J1") (pin "8") (pinfunction "8_8") (pintype "passive"))
    )
    (net (code "41") (name "unconnected-(J1-Pad9)") (class "Default")
      (node (ref "J1") (pin "9") (pinfunction "9_9") (pintype "passive"))
    )
    (net (code "42") (name "unconnected-(J1-Pad10)") (class "Default")
      (node (ref "J1") (pin "10") (pinfunction "10_10") (pintype "passive"))
    )
    (net (code "43") (name "unconnected-(J1-Pad11)") (class "Default")
      (node (ref "J1") (pin "11") (pinfunction "11_11") (pintype "passive"))
    )
    (net (code "44") (name "unconnected-(J1-Pad12)") (class "Default")
      (node (ref "J1") (pin "12") (pinfunction "12_12") (pintype "passive"))
    )
    (net (code "45") (name "unconnected-(J1-Pad13)") (class "Default")
      (node (ref "J1") (pin "13") (pinfunction "13_13") (pintype "passive"))
    )
    (net (code "46") (name "unconnected-(J1-Pad14)") (class "Default")
      (node (ref "J1") (pin "14") (pinfunction "14_14") (pintype "passive"))
    )
    (net (code "47") (name "unconnected-(J1-Pad15)") (class "Default")
      (node (ref "J1") (pin "15") (pinfunction "15_15") (pintype "passive"))
    )
    (net (code "48") (name "unconnected-(J1-Pad16)") (class "Default")
      (node (ref "J1") (pin "16") (pinfunction "16_16") (pintype "passive"))
    )
    (net (code "49") (name "unconnected-(J1-Pad17)") (class "Default")
      (node (ref "J1") (pin "17") (pinfunction "17_17") (pintype "passive"))
    )
    (net (code "50") (name "unconnected-(J1-Pad18)") (class "Default")
      (node (ref "J1") (pin "18") (pinfunction "18_18") (pintype "passive"))
    )
    (net (code "51") (name "unconnected-(U2-ST-Pad5)") (class "Default")
      (node (ref "U2") (pin "5") (pinfunction "ST_5") (pintype "input"))
    )
    (net (code "52") (name "unconnected-(U3-ST-Pad5)") (class "Default")
      (node (ref "U3") (pin "5") (pinfunction "ST_5") (pintype "input"))
    )
  )
)
